# 5V_REG.net
KiCad netlist of a schematic drawn in Altium Designer
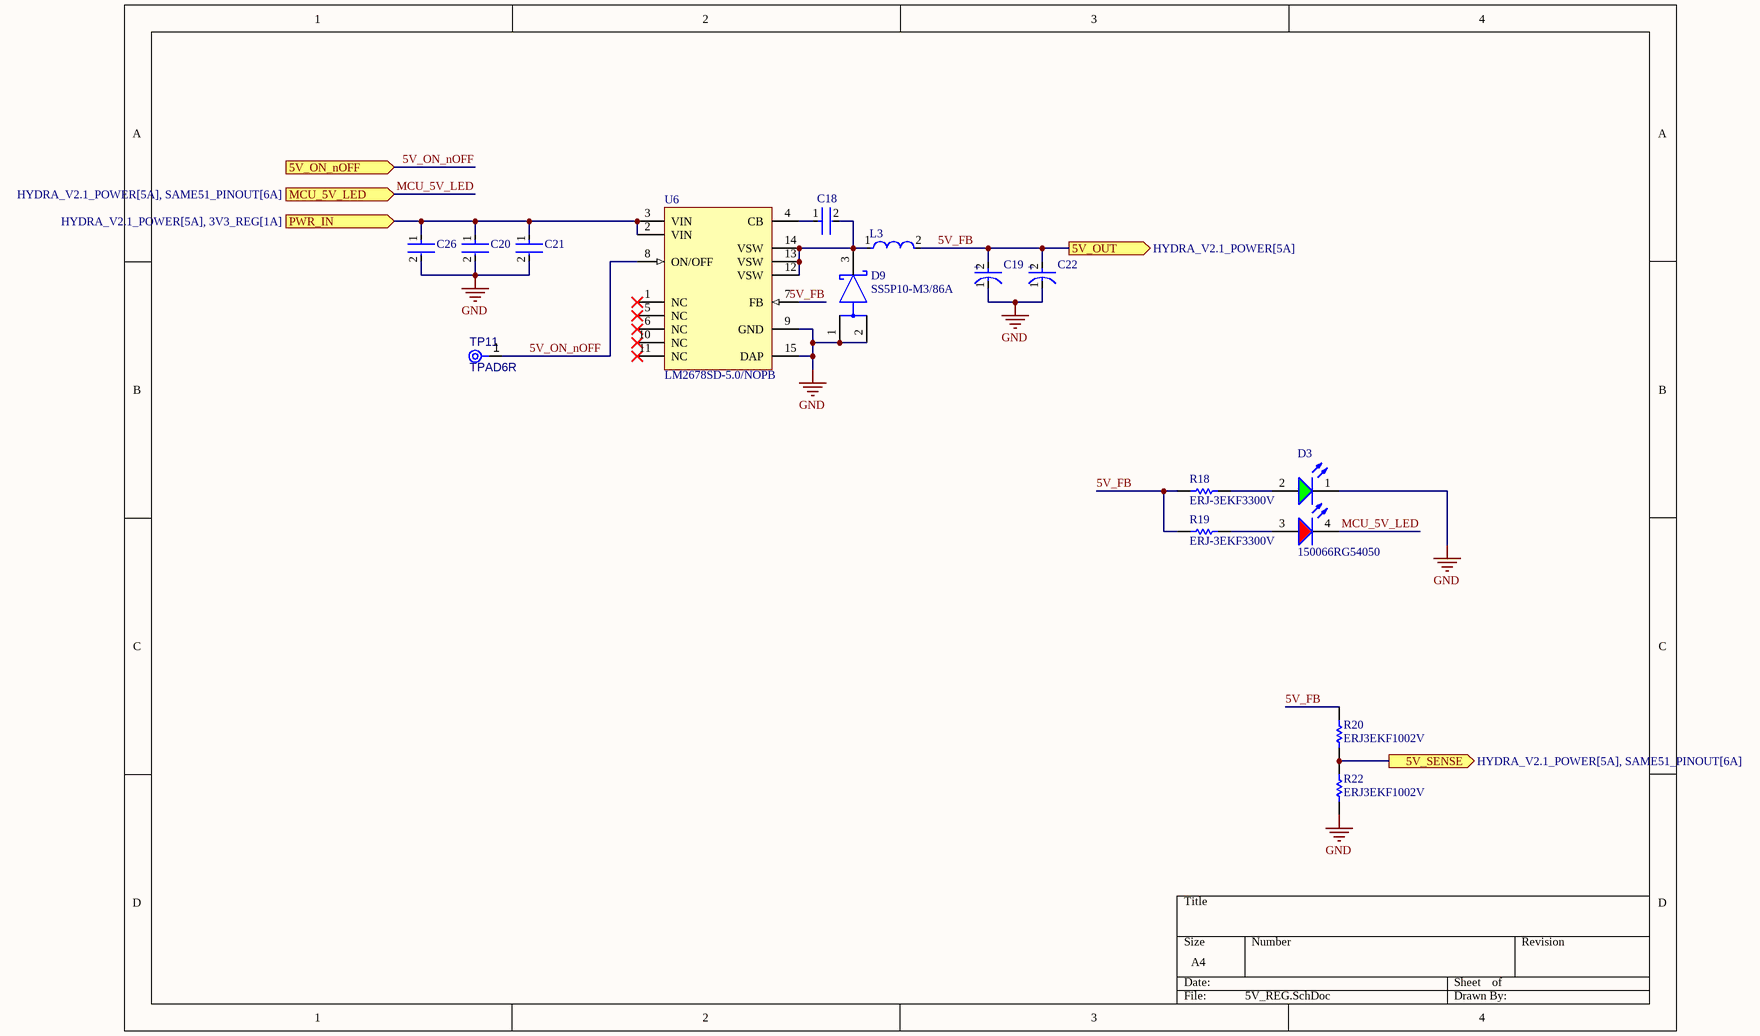
[diagram p0: 5V_REG.SchDoc]

(export (version "E")
  (design (tool "Eeschema 10.0.6"))
  (components
    (comp (ref "C18")
      (value "C0805C103J5RACTU")
      (footprint "FP-C0805C-DN-MFG")
      (description "CAP CER 10000PF 50V X7R 0805")
      (fields
        (field (name "MANUFACTURER") "KEMET")
        (field (name "OCTOPART") "https://octopart.com/c0805c103j5ractu-kemet-133473")
      )
      (libsource (lib "Altium Content Vault") (part "b4654b650e69147ec39a6b967a45e02"))
    )
    (comp (ref "C19")
      (value "10TPC68M")
      (footprint "FP-POSCAP-D2-MFG")
      (description "Molded Tantalum Polymer Capacitor 68uF 20% 10V life 2000Hours SMD 2917")
      (fields (field (name "VOLTAGE") "10V") (field (name "TOLERANCE") "20%"))
      (libsource (lib "Altium Content Vault") (part "a00bbbee19879c290e62620ae7e47b1"))
    )
    (comp (ref "C20")
      (value "C2012X5R1V156M125AC")
      (footprint "FP-C2012-125-0_2-MFG")
      (description "Multilayer Ceramic Capacitors 15μF ±20% 35V X5R SMD 0805")
      (fields (field (name "TOLERANCE") "20%"))
      (libsource (lib "Altium Content Vault") (part "b4654b650e69147ec39a6b967a45e02"))
    )
    (comp (ref "C21")
      (value "C2012X5R1V156M125AC")
      (footprint "FP-C2012-125-0_2-MFG")
      (description "Multilayer Ceramic Capacitors 15μF ±20% 35V X5R SMD 0805")
      (fields (field (name "TOLERANCE") "20%"))
      (libsource (lib "Altium Content Vault") (part "b4654b650e69147ec39a6b967a45e02"))
    )
    (comp (ref "C22")
      (value "10TPC68M")
      (footprint "FP-POSCAP-D2-MFG")
      (description "Molded Tantalum Polymer Capacitor 68uF 20% 10V life 2000Hours SMD 2917")
      (fields (field (name "VOLTAGE") "10V") (field (name "TOLERANCE") "20%"))
      (libsource (lib "Altium Content Vault") (part "a00bbbee19879c290e62620ae7e47b1"))
    )
    (comp (ref "C26")
      (value "C2012X5R1V156M125AC")
      (footprint "FP-C2012-125-0_2-MFG")
      (description "Multilayer Ceramic Capacitors 15μF ±20% 35V X5R SMD 0805")
      (fields (field (name "TOLERANCE") "20%"))
      (libsource (lib "Altium Content Vault") (part "b4654b650e69147ec39a6b967a45e02"))
    )
    (comp (ref "D3")
      (value "150066RG54050")
      (footprint "WL-SBCD_0606")
      (description "Led, Red/Grn, 180Mcd/230Mcd, 624Nm/525Nm Rohs Compliant: Yes")
      (libsource (lib "uORocketry Hardware") (part "WL-SBCD_0606_Red & Green"))
    )
    (comp (ref "D9")
      (value "SS5P10-M3/86A")
      (footprint "FP-95570-MFG")
      (description "DIODE SCHOTTKY 100V 5A TO277A")
      (libsource (lib "Altium Content Vault") (part "03725f8997c85b601c823eea96032f8"))
    )
    (comp (ref "L3")
      (value "IHLP4040DZER220M11")
      (footprint "FP-IHLP-4040DZ-FP_3_124x3-MFG")
      (description "Commercial Inductors, Low DCR Series 22uH 5A 66mΩ 20%")
      (fields (field (name "TOLERANCE") "20%"))
      (libsource (lib "Altium Content Vault") (part "725321dda6339637d4d059423bc1c3c"))
    )
    (comp (ref "R18")
      (value "ERJ-3EKF3300V")
      (footprint "RESC1608X55X30LL15T15")
      (description "Chip Resistor, 330 Ohm, +/- 1%, 0.1 W, -55 to 155 degC, 0603 (1608 Metric), RoHS, Tape and Reel")
      (libsource (lib "Altium Content Vault") (part "RES-2"))
    )
    (comp (ref "R19")
      (value "ERJ-3EKF3300V")
      (footprint "RESC1608X55X30LL15T15")
      (description "Chip Resistor, 330 Ohm, +/- 1%, 0.1 W, -55 to 155 degC, 0603 (1608 Metric), RoHS, Tape and Reel")
      (libsource (lib "Altium Content Vault") (part "RES-2"))
    )
    (comp (ref "R20")
      (value "ERJ3EKF1002V")
      (footprint "RESC1609X55X30LL15T15")
      (description "Chip Resistor, 10 KOhm, +/- 1%, 0.1 W, -55 to 155 degC, 0603 (1608 Metric), RoHS, Tape and Reel")
      (fields (field (name "TOLERANCE") "1%") (field (name "MANUFACTURER") "Panasonic"))
      (libsource (lib "Altium Content Vault") (part "RES-2"))
    )
    (comp (ref "R22")
      (value "ERJ3EKF1002V")
      (footprint "RESC1609X55X30LL15T15")
      (description "Chip Resistor, 10 KOhm, +/- 1%, 0.1 W, -55 to 155 degC, 0603 (1608 Metric), RoHS, Tape and Reel")
      (fields (field (name "TOLERANCE") "1%") (field (name "MANUFACTURER") "Panasonic"))
      (libsource (lib "Altium Content Vault") (part "RES-2"))
    )
    (comp (ref "TP11")
      (value "TPAD6R")
      (footprint "TP06R")
      (description "0.6mm round")
      (libsource (lib "uORocketry Hardware") (part "CMP-001-0001-4"))
    )
    (comp (ref "U6")
      (value "LM2678SD-5.0/NOPB")
      (footprint "NHM0014A_V")
      (description "SIMPLE SWITCHER® High Efficiency 5A Step-Down Voltage Regulator, 14-pin LLP, Pb-Free")
      (fields (field (name "MANUFACTURER") "Texas Instruments"))
      (libsource (lib "Altium Content Vault") (part "PM-REG-LM2678SD"))
    )
  )
  (nets
    (net (code "1") (name "/5V_FB") (class "Default")
      (node (ref "C19") (pin "2") (pinfunction "A_2") (pintype "passive"))
      (node (ref "C22") (pin "2") (pinfunction "A_2") (pintype "passive"))
      (node (ref "L3") (pin "2") (pinfunction "2_2") (pintype "passive"))
      (node (ref "R18") (pin "1") (pinfunction "1_1") (pintype "passive"))
      (node (ref "R19") (pin "1") (pinfunction "1_1") (pintype "passive"))
      (node (ref "R20") (pin "2") (pinfunction "2_2") (pintype "passive"))
      (node (ref "U6") (pin "7") (pinfunction "FB_7") (pintype "input"))
    )
    (net (code "2") (name "/5V_ON_nOFF") (class "Default")
      (node (ref "TP11") (pin "1") (pinfunction "TP_1") (pintype "passive"))
      (node (ref "U6") (pin "8") (pinfunction "ON/OFF_8") (pintype "input"))
    )
    (net (code "3") (name "/5V_SENSE") (class "Default")
      (node (ref "R20") (pin "1") (pinfunction "1_1") (pintype "passive"))
      (node (ref "R22") (pin "2") (pinfunction "2_2") (pintype "passive"))
    )
    (net (code "4") (name "/MCU_5V_LED") (class "Default")
      (node (ref "D3") (pin "4") (pinfunction "K_4") (pintype "passive"))
    )
    (net (code "5") (name "/PWR_IN") (class "Default")
      (node (ref "C20") (pin "1") (pinfunction "1_1") (pintype "passive"))
      (node (ref "C21") (pin "1") (pinfunction "1_1") (pintype "passive"))
      (node (ref "C26") (pin "1") (pinfunction "1_1") (pintype "passive"))
      (node (ref "U6") (pin "2") (pinfunction "VIN_2") (pintype "power_in"))
      (node (ref "U6") (pin "3") (pinfunction "VIN_3") (pintype "power_in"))
    )
    (net (code "6") (name "GND") (class "Default")
      (node (ref "C19") (pin "1") (pinfunction "C_1") (pintype "passive"))
      (node (ref "C20") (pin "2") (pinfunction "2_2") (pintype "passive"))
      (node (ref "C21") (pin "2") (pinfunction "2_2") (pintype "passive"))
      (node (ref "C22") (pin "1") (pinfunction "C_1") (pintype "passive"))
      (node (ref "C26") (pin "2") (pinfunction "2_2") (pintype "passive"))
      (node (ref "D3") (pin "1") (pinfunction "K_1") (pintype "passive"))
      (node (ref "D9") (pin "1") (pinfunction "A_1") (pintype "passive"))
      (node (ref "D9") (pin "2") (pinfunction "A_2") (pintype "passive"))
      (node (ref "R22") (pin "1") (pinfunction "1_1") (pintype "passive"))
      (node (ref "U6") (pin "15") (pinfunction "DAP_15") (pintype "power_in"))
      (node (ref "U6") (pin "9") (pinfunction "GND_9") (pintype "power_in"))
    )
    (net (code "7") (name "Net-(D3-A-Pad2)") (class "Default")
      (node (ref "D3") (pin "2") (pinfunction "A_2") (pintype "passive"))
      (node (ref "R18") (pin "2") (pinfunction "2_2") (pintype "passive"))
    )
    (net (code "8") (name "Net-(D3-A-Pad3)") (class "Default")
      (node (ref "D3") (pin "3") (pinfunction "A_3") (pintype "passive"))
      (node (ref "R19") (pin "2") (pinfunction "2_2") (pintype "passive"))
    )
    (net (code "9") (name "Net-(D9-C)") (class "Default")
      (node (ref "C18") (pin "2") (pinfunction "2_2") (pintype "passive"))
      (node (ref "D9") (pin "3") (pinfunction "C_3") (pintype "passive"))
      (node (ref "L3") (pin "1") (pinfunction "1_1") (pintype "passive"))
      (node (ref "U6") (pin "12") (pinfunction "VSW_12") (pintype "power_in"))
      (node (ref "U6") (pin "13") (pinfunction "VSW_13") (pintype "power_in"))
      (node (ref "U6") (pin "14") (pinfunction "VSW_14") (pintype "power_in"))
    )
    (net (code "10") (name "Net-(U6-CB)") (class "Default")
      (node (ref "C18") (pin "1") (pinfunction "1_1") (pintype "passive"))
      (node (ref "U6") (pin "4") (pinfunction "CB_4") (pintype "passive"))
    )
    (net (code "11") (name "unconnected-(U6-NC-Pad1)") (class "Default")
      (node (ref "U6") (pin "1") (pinfunction "NC_1") (pintype "passive+no_connect"))
    )
    (net (code "12") (name "unconnected-(U6-NC-Pad5)") (class "Default")
      (node (ref "U6") (pin "5") (pinfunction "NC_5") (pintype "passive+no_connect"))
    )
    (net (code "13") (name "unconnected-(U6-NC-Pad6)") (class "Default")
      (node (ref "U6") (pin "6") (pinfunction "NC_6") (pintype "passive+no_connect"))
    )
    (net (code "14") (name "unconnected-(U6-NC-Pad10)") (class "Default")
      (node (ref "U6") (pin "10") (pinfunction "NC_10") (pintype "passive+no_connect"))
    )
    (net (code "15") (name "unconnected-(U6-NC-Pad11)") (class "Default")
      (node (ref "U6") (pin "11") (pinfunction "NC_11") (pintype "passive+no_connect"))
    )
  )
)
